# Useless_USB_Gift_Board.net
KiCad netlist of a schematic drawn in EAGLE
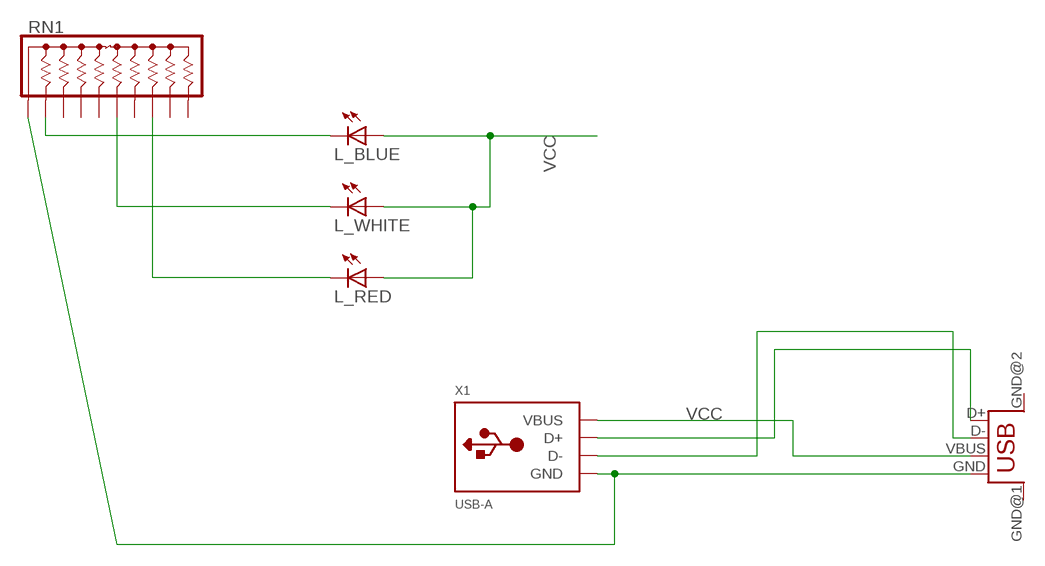
[diagram p0: schematic, sheet 1]

(export (version "E")
  (design (tool "Eeschema 10.0.6"))
  (components
    (comp (ref "L_BLUE")
      (value "LED5MM")
      (footprint "eagle-import:LED5MM")
      (libsource (lib "eagle-import") (part "LED5MM"))
    )
    (comp (ref "L_RED")
      (value "LED5MM")
      (footprint "eagle-import:LED5MM")
      (libsource (lib "eagle-import") (part "LED5MM"))
    )
    (comp (ref "L_WHITE")
      (value "LED5MM")
      (footprint "eagle-import:LED5MM")
      (libsource (lib "eagle-import") (part "LED5MM"))
    )
    (comp (ref "RN1")
      (value "4610X")
      (footprint "eagle-import:SIP10")
      (libsource (lib "eagle-import") (part "4610X"))
    )
    (comp (ref "U$1")
      (value "USB")
      (footprint "eagle-import:USB-FEMALE-A-PTH")
      (libsource (lib "eagle-import") (part "USB"))
    )
    (comp (ref "X1")
      (value "USB-A")
      (footprint "eagle-import:MOLEX_480371000")
      (libsource (lib "eagle-import") (part "USB-A"))
    )
  )
  (nets
    (net (code "1") (name "/VCC") (class "Default")
      (node (ref "L_BLUE") (pin "A") (pinfunction "A_A") (pintype "passive"))
      (node (ref "L_RED") (pin "A") (pinfunction "A_A") (pintype "passive"))
      (node (ref "L_WHITE") (pin "A") (pinfunction "A_A") (pintype "passive"))
      (node (ref "U$1") (pin "VBUS") (pinfunction "VBUS_VBUS") (pintype "bidirectional"))
      (node (ref "X1") (pin "1") (pinfunction "VBUS_1") (pintype "power_in"))
    )
    (net (code "2") (name "Net-(L_BLUE-C)") (class "Default")
      (node (ref "L_BLUE") (pin "K") (pinfunction "C_K") (pintype "passive"))
      (node (ref "RN1") (pin "2") (pinfunction "2_2") (pintype "passive"))
    )
    (net (code "3") (name "Net-(L_RED-C)") (class "Default")
      (node (ref "L_RED") (pin "K") (pinfunction "C_K") (pintype "passive"))
      (node (ref "RN1") (pin "8") (pinfunction "8_8") (pintype "passive"))
    )
    (net (code "4") (name "Net-(L_WHITE-C)") (class "Default")
      (node (ref "L_WHITE") (pin "K") (pinfunction "C_K") (pintype "passive"))
      (node (ref "RN1") (pin "6") (pinfunction "6_6") (pintype "passive"))
    )
    (net (code "5") (name "Net-(X1-D+)") (class "Default")
      (node (ref "U$1") (pin "D+") (pinfunction "D+_D+") (pintype "bidirectional"))
      (node (ref "X1") (pin "3") (pinfunction "D+_3") (pintype "bidirectional"))
    )
    (net (code "6") (name "Net-(X1-D-)") (class "Default")
      (node (ref "U$1") (pin "D-") (pinfunction "D-_D-") (pintype "bidirectional"))
      (node (ref "X1") (pin "2") (pinfunction "D-_2") (pintype "bidirectional"))
    )
    (net (code "7") (name "Net-(X1-GND)") (class "Default")
      (node (ref "RN1") (pin "1") (pinfunction "1_1") (pintype "passive"))
      (node (ref "U$1") (pin "GND") (pinfunction "GND_GND") (pintype "bidirectional"))
      (node (ref "X1") (pin "4") (pinfunction "GND_4") (pintype "power_in"))
    )
    (net (code "8") (name "unconnected-(RN1-Pad3)") (class "Default")
      (node (ref "RN1") (pin "3") (pinfunction "3_3") (pintype "passive"))
    )
    (net (code "9") (name "unconnected-(RN1-Pad4)") (class "Default")
      (node (ref "RN1") (pin "4") (pinfunction "4_4") (pintype "passive"))
    )
    (net (code "10") (name "unconnected-(RN1-Pad5)") (class "Default")
      (node (ref "RN1") (pin "5") (pinfunction "5_5") (pintype "passive"))
    )
    (net (code "11") (name "unconnected-(RN1-Pad7)") (class "Default")
      (node (ref "RN1") (pin "7") (pinfunction "7_7") (pintype "passive"))
    )
    (net (code "12") (name "unconnected-(RN1-Pad9)") (class "Default")
      (node (ref "RN1") (pin "9") (pinfunction "9_9") (pintype "passive"))
    )
    (net (code "13") (name "unconnected-(RN1-Pad10)") (class "Default")
      (node (ref "RN1") (pin "10") (pinfunction "10_10") (pintype "passive"))
    )
    (net (code "14") (name "unconnected-(U$1-GND-PadGND@1)") (class "Default")
      (node (ref "U$1") (pin "GND@1") (pinfunction "GND_GND@1") (pintype "bidirectional"))
    )
    (net (code "15") (name "unconnected-(U$1-GND-PadGND@2)") (class "Default")
      (node (ref "U$1") (pin "GND@2") (pinfunction "GND_GND@2") (pintype "bidirectional"))
    )
  )
)
